# di.net
KiCad netlist of a schematic drawn in Altium Designer
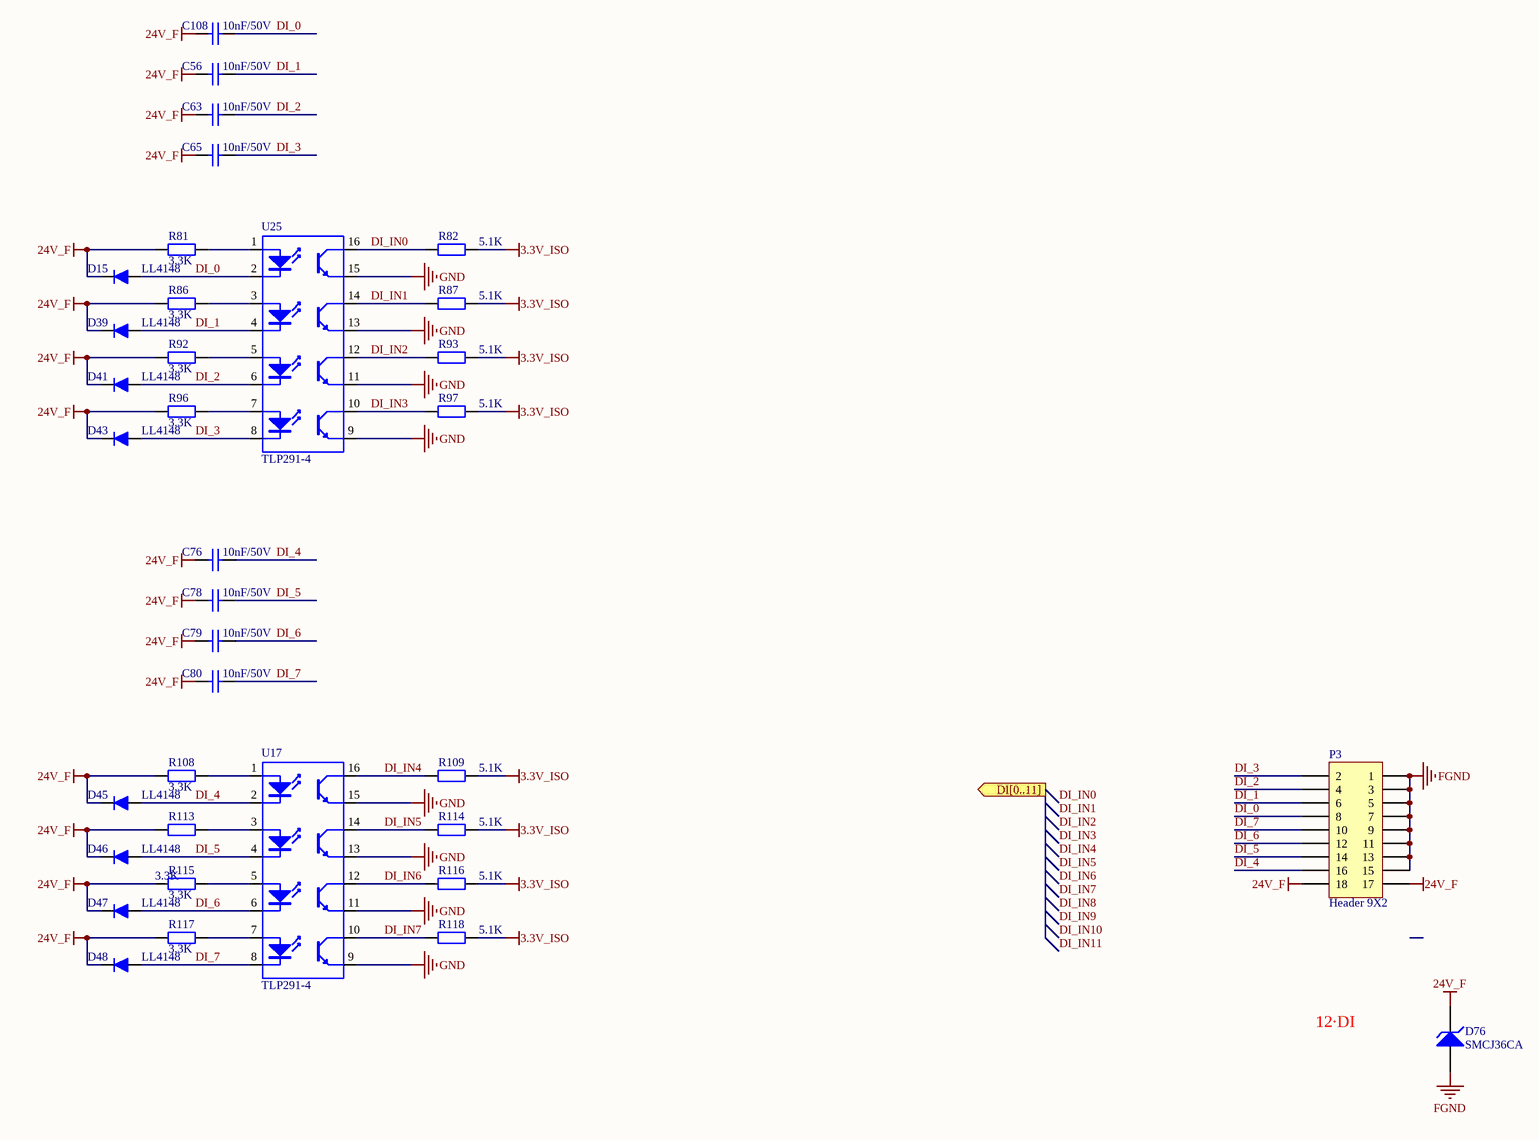
[diagram p0: di.SchDoc]

(export (version "E")
  (design (tool "Eeschema 10.0.6"))
  (components
    (comp (ref "C56")
      (value "10nF/50V")
      (footprint "0603C")
      (description "Capacitor")
      (fields (field (name "PUBLISHER") "Altium Limited"))
      (libsource (lib "Miscellaneous Devices") (part "Cap"))
    )
    (comp (ref "C63")
      (value "10nF/50V")
      (footprint "0603C")
      (description "Capacitor")
      (fields (field (name "PUBLISHER") "Altium Limited"))
      (libsource (lib "Miscellaneous Devices") (part "Cap"))
    )
    (comp (ref "C65")
      (value "10nF/50V")
      (footprint "0603C")
      (description "Capacitor")
      (fields (field (name "PUBLISHER") "Altium Limited"))
      (libsource (lib "Miscellaneous Devices") (part "Cap"))
    )
    (comp (ref "C76")
      (value "10nF/50V")
      (footprint "0603C")
      (description "Capacitor")
      (fields (field (name "PUBLISHER") "Altium Limited"))
      (libsource (lib "Miscellaneous Devices") (part "Cap"))
    )
    (comp (ref "C78")
      (value "10nF/50V")
      (footprint "0603C")
      (description "Capacitor")
      (fields (field (name "PUBLISHER") "Altium Limited"))
      (libsource (lib "Miscellaneous Devices") (part "Cap"))
    )
    (comp (ref "C79")
      (value "10nF/50V")
      (footprint "0603C")
      (description "Capacitor")
      (fields (field (name "PUBLISHER") "Altium Limited"))
      (libsource (lib "Miscellaneous Devices") (part "Cap"))
    )
    (comp (ref "C80")
      (value "10nF/50V")
      (footprint "0603C")
      (description "Capacitor")
      (fields (field (name "PUBLISHER") "Altium Limited"))
      (libsource (lib "Miscellaneous Devices") (part "Cap"))
    )
    (comp (ref "C108")
      (value "10nF/50V")
      (footprint "0603C")
      (description "Capacitor")
      (fields (field (name "PUBLISHER") "Altium Limited"))
      (libsource (lib "Miscellaneous Devices") (part "Cap"))
    )
    (comp (ref "D15")
      (value "LL4148")
      (footprint "DO-213AB/LL34/MiniMELF")
      (description "VISHAY,LL4148,圆柱体MiniMELF100V/2A,ROHS")
      (libsource (lib "Device2018") (part "LL4148"))
    )
    (comp (ref "D39")
      (value "LL4148")
      (footprint "DO-213AB/LL34/MiniMELF")
      (description "VISHAY,LL4148,圆柱体MiniMELF100V/2A,ROHS")
      (libsource (lib "Device2018") (part "LL4148"))
    )
    (comp (ref "D41")
      (value "LL4148")
      (footprint "DO-213AB/LL34/MiniMELF")
      (description "VISHAY,LL4148,圆柱体MiniMELF100V/2A,ROHS")
      (libsource (lib "Device2018") (part "LL4148"))
    )
    (comp (ref "D43")
      (value "LL4148")
      (footprint "DO-213AB/LL34/MiniMELF")
      (description "VISHAY,LL4148,圆柱体MiniMELF100V/2A,ROHS")
      (libsource (lib "Device2018") (part "LL4148"))
    )
    (comp (ref "D45")
      (value "LL4148")
      (footprint "DO-213AB/LL34/MiniMELF")
      (description "VISHAY,LL4148,圆柱体MiniMELF100V/2A,ROHS")
      (libsource (lib "Device2018") (part "LL4148"))
    )
    (comp (ref "D46")
      (value "LL4148")
      (footprint "DO-213AB/LL34/MiniMELF")
      (description "VISHAY,LL4148,圆柱体MiniMELF100V/2A,ROHS")
      (libsource (lib "Device2018") (part "LL4148"))
    )
    (comp (ref "D47")
      (value "LL4148")
      (footprint "DO-213AB/LL34/MiniMELF")
      (description "VISHAY,LL4148,圆柱体MiniMELF100V/2A,ROHS")
      (libsource (lib "Device2018") (part "LL4148"))
    )
    (comp (ref "D48")
      (value "LL4148")
      (footprint "DO-213AB/LL34/MiniMELF")
      (description "VISHAY,LL4148,圆柱体MiniMELF100V/2A,ROHS")
      (libsource (lib "Device2018") (part "LL4148"))
    )
    (comp (ref "D76")
      (value "SMCJ36CA")
      (footprint "smc")
      (description "SMBJ36CA")
      (fields (field (name "PUBLISHER") "Altium Limited"))
      (libsource (lib "Miscellaneous Devices") (part "D Zener"))
    )
    (comp (ref "P3")
      (value "Header 9X2")
      (footprint "XH2.54_2x9")
      (description "Header, 9-Pin, Dual row")
      (fields (field (name "PUBLISHER") "Altium Limited"))
      (libsource (lib "Miscellaneous Connectors") (part "Header 9X2"))
    )
    (comp (ref "R81") (value "3.3K") (footprint "0603R") (libsource (lib "MQlibrary") (part "Res0805M")))
    (comp (ref "R82") (value "5.1K") (footprint "0603R") (libsource (lib "MQlibrary") (part "Res0805M")))
    (comp (ref "R86") (value "3.3K") (footprint "0603R") (libsource (lib "MQlibrary") (part "Res0805M")))
    (comp (ref "R87") (value "5.1K") (footprint "0603R") (libsource (lib "MQlibrary") (part "Res0805M")))
    (comp (ref "R92") (value "3.3K") (footprint "0603R") (libsource (lib "MQlibrary") (part "Res0805M")))
    (comp (ref "R93") (value "5.1K") (footprint "0603R") (libsource (lib "MQlibrary") (part "Res0805M")))
    (comp (ref "R96") (value "3.3K") (footprint "0603R") (libsource (lib "MQlibrary") (part "Res0805M")))
    (comp (ref "R97") (value "5.1K") (footprint "0603R") (libsource (lib "MQlibrary") (part "Res0805M")))
    (comp (ref "R108") (value "3.3K") (footprint "0603R") (libsource (lib "MQlibrary") (part "Res0805M")))
    (comp (ref "R109") (value "5.1K") (footprint "0603R") (libsource (lib "MQlibrary") (part "Res0805M")))
    (comp (ref "R113") (value "3.3K") (footprint "0603R") (libsource (lib "MQlibrary") (part "Res0805M")))
    (comp (ref "R114") (value "5.1K") (footprint "0603R") (libsource (lib "MQlibrary") (part "Res0805M")))
    (comp (ref "R115") (value "3.3K") (footprint "0603R") (libsource (lib "MQlibrary") (part "Res0805M")))
    (comp (ref "R116") (value "5.1K") (footprint "0603R") (libsource (lib "MQlibrary") (part "Res0805M")))
    (comp (ref "R117") (value "3.3K") (footprint "0603R") (libsource (lib "MQlibrary") (part "Res0805M")))
    (comp (ref "R118") (value "5.1K") (footprint "0603R") (libsource (lib "MQlibrary") (part "Res0805M")))
    (comp (ref "U17") (value "TLP291-4") (footprint "SOP16-T") (libsource (lib "DI16") (part "TLP281-4")))
    (comp (ref "U25") (value "TLP291-4") (footprint "SOP16-T") (libsource (lib "DI16") (part "TLP281-4")))
  )
  (nets
    (net (code "14") (name "/DI_0") (class "Default")
      (node (ref "C108") (pin "2") (pinfunction "2_2") (pintype "passive"))
      (node (ref "D15") (pin "2") (pinfunction "2_2") (pintype "passive"))
      (node (ref "P3") (pin "8") (pinfunction "8_8") (pintype "passive"))
      (node (ref "U25") (pin "2") (pinfunction "K_2") (pintype "passive"))
    )
    (net (code "15") (name "/DI_1") (class "Default")
      (node (ref "C56") (pin "2") (pinfunction "2_2") (pintype "passive"))
      (node (ref "D39") (pin "2") (pinfunction "2_2") (pintype "passive"))
      (node (ref "P3") (pin "6") (pinfunction "6_6") (pintype "passive"))
      (node (ref "U25") (pin "4") (pinfunction "K_4") (pintype "passive"))
    )
    (net (code "16") (name "/DI_2") (class "Default")
      (node (ref "C63") (pin "2") (pinfunction "2_2") (pintype "passive"))
      (node (ref "D41") (pin "2") (pinfunction "2_2") (pintype "passive"))
      (node (ref "P3") (pin "4") (pinfunction "4_4") (pintype "passive"))
      (node (ref "U25") (pin "6") (pinfunction "K_6") (pintype "passive"))
    )
    (net (code "17") (name "/DI_3") (class "Default")
      (node (ref "C65") (pin "2") (pinfunction "2_2") (pintype "passive"))
      (node (ref "D43") (pin "2") (pinfunction "2_2") (pintype "passive"))
      (node (ref "P3") (pin "2") (pinfunction "2_2") (pintype "passive"))
      (node (ref "U25") (pin "8") (pinfunction "K_8") (pintype "passive"))
    )
    (net (code "18") (name "/DI_4") (class "Default")
      (node (ref "C76") (pin "2") (pinfunction "2_2") (pintype "passive"))
      (node (ref "D45") (pin "2") (pinfunction "2_2") (pintype "passive"))
      (node (ref "P3") (pin "16") (pinfunction "16_16") (pintype "passive"))
      (node (ref "U17") (pin "2") (pinfunction "K_2") (pintype "passive"))
    )
    (net (code "19") (name "/DI_5") (class "Default")
      (node (ref "C78") (pin "2") (pinfunction "2_2") (pintype "passive"))
      (node (ref "D46") (pin "2") (pinfunction "2_2") (pintype "passive"))
      (node (ref "P3") (pin "14") (pinfunction "14_14") (pintype "passive"))
      (node (ref "U17") (pin "4") (pinfunction "K_4") (pintype "passive"))
    )
    (net (code "20") (name "/DI_6") (class "Default")
      (node (ref "C79") (pin "2") (pinfunction "2_2") (pintype "passive"))
      (node (ref "D47") (pin "2") (pinfunction "2_2") (pintype "passive"))
      (node (ref "P3") (pin "12") (pinfunction "12_12") (pintype "passive"))
      (node (ref "U17") (pin "6") (pinfunction "K_6") (pintype "passive"))
    )
    (net (code "21") (name "/DI_7") (class "Default")
      (node (ref "C80") (pin "2") (pinfunction "2_2") (pintype "passive"))
      (node (ref "D48") (pin "2") (pinfunction "2_2") (pintype "passive"))
      (node (ref "P3") (pin "10") (pinfunction "10_10") (pintype "passive"))
      (node (ref "U17") (pin "8") (pinfunction "K_8") (pintype "passive"))
    )
    (net (code "22") (name "/DI_IN0") (class "Default")
      (node (ref "R82") (pin "2") (pinfunction "2_2") (pintype "passive"))
      (node (ref "U25") (pin "16") (pinfunction "C_16") (pintype "passive"))
    )
    (net (code "23") (name "/DI_IN1") (class "Default")
      (node (ref "R87") (pin "2") (pinfunction "2_2") (pintype "passive"))
      (node (ref "U25") (pin "14") (pinfunction "C_14") (pintype "passive"))
    )
    (net (code "24") (name "/DI_IN2") (class "Default")
      (node (ref "R93") (pin "2") (pinfunction "2_2") (pintype "passive"))
      (node (ref "U25") (pin "12") (pinfunction "C_12") (pintype "passive"))
    )
    (net (code "25") (name "/DI_IN3") (class "Default")
      (node (ref "R97") (pin "2") (pinfunction "2_2") (pintype "passive"))
      (node (ref "U25") (pin "10") (pinfunction "C_10") (pintype "passive"))
    )
    (net (code "26") (name "/DI_IN4") (class "Default")
      (node (ref "R109") (pin "2") (pinfunction "2_2") (pintype "passive"))
      (node (ref "U17") (pin "16") (pinfunction "C_16") (pintype "passive"))
    )
    (net (code "27") (name "/DI_IN5") (class "Default")
      (node (ref "R114") (pin "2") (pinfunction "2_2") (pintype "passive"))
      (node (ref "U17") (pin "14") (pinfunction "C_14") (pintype "passive"))
    )
    (net (code "28") (name "/DI_IN6") (class "Default")
      (node (ref "R116") (pin "2") (pinfunction "2_2") (pintype "passive"))
      (node (ref "U17") (pin "12") (pinfunction "C_12") (pintype "passive"))
    )
    (net (code "29") (name "/DI_IN7") (class "Default")
      (node (ref "R118") (pin "2") (pinfunction "2_2") (pintype "passive"))
      (node (ref "U17") (pin "10") (pinfunction "C_10") (pintype "passive"))
    )
    (net (code "34") (name "3.3V_ISO") (class "Default")
      (node (ref "R109") (pin "1") (pinfunction "1_1") (pintype "passive"))
      (node (ref "R114") (pin "1") (pinfunction "1_1") (pintype "passive"))
      (node (ref "R116") (pin "1") (pinfunction "1_1") (pintype "passive"))
      (node (ref "R118") (pin "1") (pinfunction "1_1") (pintype "passive"))
      (node (ref "R82") (pin "1") (pinfunction "1_1") (pintype "passive"))
      (node (ref "R87") (pin "1") (pinfunction "1_1") (pintype "passive"))
      (node (ref "R93") (pin "1") (pinfunction "1_1") (pintype "passive"))
      (node (ref "R97") (pin "1") (pinfunction "1_1") (pintype "passive"))
    )
    (net (code "35") (name "24V_F") (class "Default")
      (node (ref "C108") (pin "1") (pinfunction "1_1") (pintype "passive"))
      (node (ref "C56") (pin "1") (pinfunction "1_1") (pintype "passive"))
      (node (ref "C63") (pin "1") (pinfunction "1_1") (pintype "passive"))
      (node (ref "C65") (pin "1") (pinfunction "1_1") (pintype "passive"))
      (node (ref "C76") (pin "1") (pinfunction "1_1") (pintype "passive"))
      (node (ref "C78") (pin "1") (pinfunction "1_1") (pintype "passive"))
      (node (ref "C79") (pin "1") (pinfunction "1_1") (pintype "passive"))
      (node (ref "C80") (pin "1") (pinfunction "1_1") (pintype "passive"))
      (node (ref "D15") (pin "1") (pinfunction "1_1") (pintype "passive"))
      (node (ref "D39") (pin "1") (pinfunction "1_1") (pintype "passive"))
      (node (ref "D41") (pin "1") (pinfunction "1_1") (pintype "passive"))
      (node (ref "D43") (pin "1") (pinfunction "1_1") (pintype "passive"))
      (node (ref "D45") (pin "1") (pinfunction "1_1") (pintype "passive"))
      (node (ref "D46") (pin "1") (pinfunction "1_1") (pintype "passive"))
      (node (ref "D47") (pin "1") (pinfunction "1_1") (pintype "passive"))
      (node (ref "D48") (pin "1") (pinfunction "1_1") (pintype "passive"))
      (node (ref "D76") (pin "2") (pinfunction "K_2") (pintype "passive"))
      (node (ref "P3") (pin "17") (pinfunction "17_17") (pintype "passive"))
      (node (ref "P3") (pin "18") (pinfunction "18_18") (pintype "passive"))
      (node (ref "R108") (pin "2") (pinfunction "2_2") (pintype "passive"))
      (node (ref "R113") (pin "2") (pinfunction "2_2") (pintype "passive"))
      (node (ref "R115") (pin "2") (pinfunction "2_2") (pintype "passive"))
      (node (ref "R117") (pin "2") (pinfunction "2_2") (pintype "passive"))
      (node (ref "R81") (pin "2") (pinfunction "2_2") (pintype "passive"))
      (node (ref "R86") (pin "2") (pinfunction "2_2") (pintype "passive"))
      (node (ref "R92") (pin "2") (pinfunction "2_2") (pintype "passive"))
      (node (ref "R96") (pin "2") (pinfunction "2_2") (pintype "passive"))
    )
    (net (code "36") (name "FGND") (class "Default")
      (node (ref "D76") (pin "1") (pinfunction "A_1") (pintype "passive"))
      (node (ref "P3") (pin "1") (pinfunction "1_1") (pintype "passive"))
      (node (ref "P3") (pin "11") (pinfunction "11_11") (pintype "passive"))
      (node (ref "P3") (pin "13") (pinfunction "13_13") (pintype "passive"))
      (node (ref "P3") (pin "15") (pinfunction "15_15") (pintype "passive"))
      (node (ref "P3") (pin "3") (pinfunction "3_3") (pintype "passive"))
      (node (ref "P3") (pin "5") (pinfunction "5_5") (pintype "passive"))
      (node (ref "P3") (pin "7") (pinfunction "7_7") (pintype "passive"))
      (node (ref "P3") (pin "9") (pinfunction "9_9") (pintype "passive"))
    )
    (net (code "37") (name "GND") (class "Default")
      (node (ref "U17") (pin "11") (pinfunction "E_11") (pintype "passive"))
      (node (ref "U17") (pin "13") (pinfunction "E_13") (pintype "passive"))
      (node (ref "U17") (pin "15") (pinfunction "E_15") (pintype "passive"))
      (node (ref "U17") (pin "9") (pinfunction "E_9") (pintype "passive"))
      (node (ref "U25") (pin "11") (pinfunction "E_11") (pintype "passive"))
      (node (ref "U25") (pin "13") (pinfunction "E_13") (pintype "passive"))
      (node (ref "U25") (pin "15") (pinfunction "E_15") (pintype "passive"))
      (node (ref "U25") (pin "9") (pinfunction "E_9") (pintype "passive"))
    )
    (net (code "38") (name "Net-(R81-Pad1)") (class "Default")
      (node (ref "R81") (pin "1") (pinfunction "1_1") (pintype "passive"))
      (node (ref "U25") (pin "1") (pinfunction "A_1") (pintype "passive"))
    )
    (net (code "39") (name "Net-(R86-Pad1)") (class "Default")
      (node (ref "R86") (pin "1") (pinfunction "1_1") (pintype "passive"))
      (node (ref "U25") (pin "3") (pinfunction "A_3") (pintype "passive"))
    )
    (net (code "40") (name "Net-(R92-Pad1)") (class "Default")
      (node (ref "R92") (pin "1") (pinfunction "1_1") (pintype "passive"))
      (node (ref "U25") (pin "5") (pinfunction "A_5") (pintype "passive"))
    )
    (net (code "41") (name "Net-(R96-Pad1)") (class "Default")
      (node (ref "R96") (pin "1") (pinfunction "1_1") (pintype "passive"))
      (node (ref "U25") (pin "7") (pinfunction "A_7") (pintype "passive"))
    )
    (net (code "42") (name "Net-(R108-Pad1)") (class "Default")
      (node (ref "R108") (pin "1") (pinfunction "1_1") (pintype "passive"))
      (node (ref "U17") (pin "1") (pinfunction "A_1") (pintype "passive"))
    )
    (net (code "43") (name "Net-(R113-Pad1)") (class "Default")
      (node (ref "R113") (pin "1") (pinfunction "1_1") (pintype "passive"))
      (node (ref "U17") (pin "3") (pinfunction "A_3") (pintype "passive"))
    )
    (net (code "44") (name "Net-(R115-Pad1)") (class "Default")
      (node (ref "R115") (pin "1") (pinfunction "1_1") (pintype "passive"))
      (node (ref "U17") (pin "5") (pinfunction "A_5") (pintype "passive"))
    )
    (net (code "45") (name "Net-(R117-Pad1)") (class "Default")
      (node (ref "R117") (pin "1") (pinfunction "1_1") (pintype "passive"))
      (node (ref "U17") (pin "7") (pinfunction "A_7") (pintype "passive"))
    )
  )
)
